# dice2.net
KiCad netlist of a schematic drawn in EAGLE
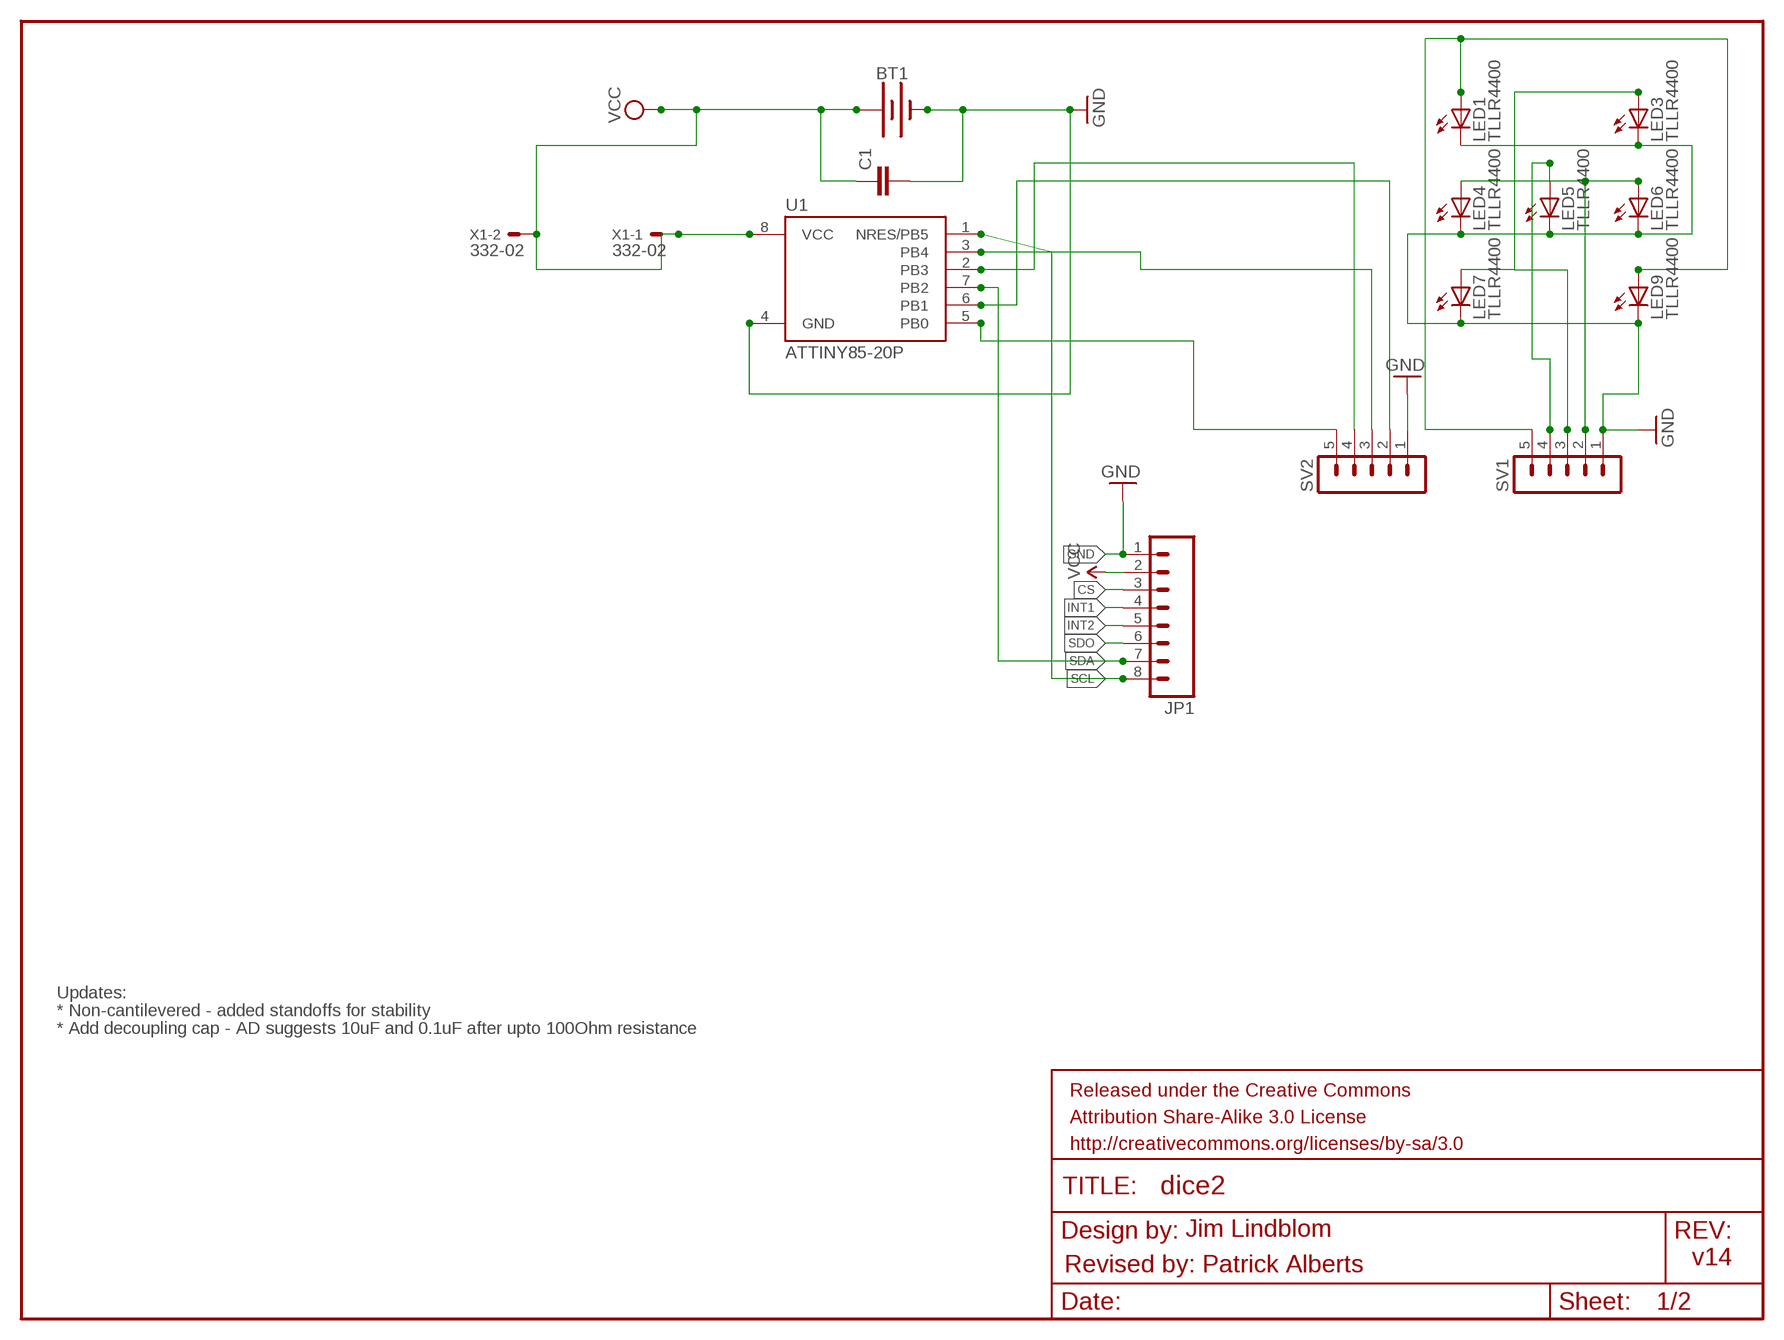
[diagram p0: schematic, sheet 1]

(export (version "E")
  (design (tool "Eeschema 10.0.6"))
  (components
    (comp (ref "BT1")
      (value "BATTERY-20MM_PTH")
      (footprint "eagle-import:BATTCOM_20MM_PTH")
      (libsource (lib "eagle-import") (part "BATTERY-20MM_PTH"))
    )
    (comp (ref "C1")
      (value "C-EU025-024X044")
      (footprint "eagle-import:C025-024X044")
      (libsource (lib "eagle-import") (part "C-EU025-024X044"))
    )
    (comp (ref "JP1")
      (value "M08")
      (footprint "eagle-import:1X08")
      (libsource (lib "eagle-import") (part "M08"))
    )
    (comp (ref "LED1")
      (value "TLLR4400")
      (footprint "eagle-import:LED3MM")
      (fields (field (name "MF") "VISHAY SEMICONDUCTOR"))
      (libsource (lib "eagle-import") (part "TLLR4400"))
    )
    (comp (ref "LED3")
      (value "TLLR4400")
      (footprint "eagle-import:LED3MM")
      (fields (field (name "MF") "VISHAY SEMICONDUCTOR"))
      (libsource (lib "eagle-import") (part "TLLR4400"))
    )
    (comp (ref "LED4")
      (value "TLLR4400")
      (footprint "eagle-import:LED3MM")
      (fields (field (name "MF") "VISHAY SEMICONDUCTOR"))
      (libsource (lib "eagle-import") (part "TLLR4400"))
    )
    (comp (ref "LED5")
      (value "TLLR4400")
      (footprint "eagle-import:LED3MM")
      (fields (field (name "MF") "VISHAY SEMICONDUCTOR"))
      (libsource (lib "eagle-import") (part "TLLR4400"))
    )
    (comp (ref "LED6")
      (value "TLLR4400")
      (footprint "eagle-import:LED3MM")
      (fields (field (name "MF") "VISHAY SEMICONDUCTOR"))
      (libsource (lib "eagle-import") (part "TLLR4400"))
    )
    (comp (ref "LED7")
      (value "TLLR4400")
      (footprint "eagle-import:LED3MM")
      (fields (field (name "MF") "VISHAY SEMICONDUCTOR"))
      (libsource (lib "eagle-import") (part "TLLR4400"))
    )
    (comp (ref "LED9")
      (value "TLLR4400")
      (footprint "eagle-import:LED3MM")
      (fields (field (name "MF") "VISHAY SEMICONDUCTOR"))
      (libsource (lib "eagle-import") (part "TLLR4400"))
    )
    (comp (ref "SV1")
      (value "MA05-1")
      (footprint "eagle-import:MA05-1")
      (libsource (lib "eagle-import") (part "MA05-1"))
    )
    (comp (ref "SV2")
      (value "MA05-1")
      (footprint "eagle-import:MA05-1")
      (libsource (lib "eagle-import") (part "MA05-1"))
    )
    (comp (ref "U1")
      (value "ATTINY85-20P")
      (footprint "eagle-import:PDIP08_300MIL")
      (libsource (lib "eagle-import") (part "ATTINY85P-20"))
    )
    (comp (ref "X1")
      (value "332-02")
      (footprint "eagle-import:332-02")
      (libsource (lib "eagle-import") (part "332-02"))
    )
  )
  (nets
    (net (code "1") (name "CS") (class "Default")
      (node (ref "JP1") (pin "3") (pinfunction "3_3") (pintype "passive"))
    )
    (net (code "2") (name "GND") (class "Default")
      (node (ref "BT1") (pin "2") (pinfunction "-_2") (pintype "power_in"))
      (node (ref "C1") (pin "2") (pinfunction "2_2") (pintype "passive"))
      (node (ref "JP1") (pin "1") (pinfunction "1_1") (pintype "passive"))
      (node (ref "LED1") (pin "K") (pinfunction "C_K") (pintype "passive"))
      (node (ref "LED3") (pin "K") (pinfunction "C_K") (pintype "passive"))
      (node (ref "LED4") (pin "K") (pinfunction "C_K") (pintype "passive"))
      (node (ref "LED5") (pin "K") (pinfunction "C_K") (pintype "passive"))
      (node (ref "LED6") (pin "K") (pinfunction "C_K") (pintype "passive"))
      (node (ref "LED7") (pin "K") (pinfunction "C_K") (pintype "passive"))
      (node (ref "LED9") (pin "K") (pinfunction "C_K") (pintype "passive"))
      (node (ref "SV1") (pin "1") (pinfunction "1_1") (pintype "passive"))
      (node (ref "SV2") (pin "1") (pinfunction "1_1") (pintype "passive"))
      (node (ref "U1") (pin "4") (pinfunction "GND_4") (pintype "power_in"))
    )
    (net (code "3") (name "INT1") (class "Default")
      (node (ref "JP1") (pin "4") (pinfunction "4_4") (pintype "passive"))
    )
    (net (code "4") (name "INT2") (class "Default")
      (node (ref "JP1") (pin "5") (pinfunction "5_5") (pintype "passive"))
    )
    (net (code "5") (name "Net-(LED1-PadA)") (class "Default")
      (node (ref "LED1") (pin "A") (pinfunction "A_A") (pintype "passive"))
      (node (ref "LED9") (pin "A") (pinfunction "A_A") (pintype "passive"))
      (node (ref "SV1") (pin "5") (pinfunction "5_5") (pintype "passive"))
    )
    (net (code "6") (name "Net-(LED3-PadA)") (class "Default")
      (node (ref "LED3") (pin "A") (pinfunction "A_A") (pintype "passive"))
      (node (ref "LED7") (pin "A") (pinfunction "A_A") (pintype "passive"))
      (node (ref "SV1") (pin "3") (pinfunction "3_3") (pintype "passive"))
    )
    (net (code "7") (name "Net-(LED4-PadA)") (class "Default")
      (node (ref "LED4") (pin "A") (pinfunction "A_A") (pintype "passive"))
      (node (ref "LED6") (pin "A") (pinfunction "A_A") (pintype "passive"))
      (node (ref "SV1") (pin "2") (pinfunction "2_2") (pintype "passive"))
    )
    (net (code "8") (name "Net-(LED5-PadA)") (class "Default")
      (node (ref "LED5") (pin "A") (pinfunction "A_A") (pintype "passive"))
      (node (ref "SV1") (pin "4") (pinfunction "4_4") (pintype "passive"))
    )
    (net (code "9") (name "Net-(U1-PB0)") (class "Default")
      (node (ref "SV2") (pin "5") (pinfunction "5_5") (pintype "passive"))
      (node (ref "U1") (pin "5") (pinfunction "PB0_5") (pintype "bidirectional"))
    )
    (net (code "10") (name "Net-(U1-PB1)") (class "Default")
      (node (ref "SV2") (pin "2") (pinfunction "2_2") (pintype "passive"))
      (node (ref "U1") (pin "6") (pinfunction "PB1_6") (pintype "bidirectional"))
    )
    (net (code "11") (name "Net-(U1-PB3)") (class "Default")
      (node (ref "SV2") (pin "4") (pinfunction "4_4") (pintype "passive"))
      (node (ref "U1") (pin "2") (pinfunction "PB3_2") (pintype "bidirectional"))
    )
    (net (code "12") (name "Net-(U1-PB4)") (class "Default")
      (node (ref "SV2") (pin "3") (pinfunction "3_3") (pintype "passive"))
      (node (ref "U1") (pin "3") (pinfunction "PB4_3") (pintype "bidirectional"))
    )
    (net (code "13") (name "SCL") (class "Default")
      (node (ref "JP1") (pin "8") (pinfunction "8_8") (pintype "passive"))
      (node (ref "U1") (pin "1") (pinfunction "NRES/PB5_1") (pintype "bidirectional"))
    )
    (net (code "14") (name "SDA") (class "Default")
      (node (ref "JP1") (pin "7") (pinfunction "7_7") (pintype "passive"))
      (node (ref "U1") (pin "7") (pinfunction "PB2_7") (pintype "bidirectional"))
    )
    (net (code "15") (name "SDO") (class "Default")
      (node (ref "JP1") (pin "6") (pinfunction "6_6") (pintype "passive"))
    )
    (net (code "16") (name "VCC") (class "Default")
      (node (ref "BT1") (pin "1") (pinfunction "+_1") (pintype "power_in"))
      (node (ref "C1") (pin "1") (pinfunction "1_1") (pintype "passive"))
      (node (ref "JP1") (pin "2") (pinfunction "2_2") (pintype "passive"))
      (node (ref "U1") (pin "8") (pinfunction "VCC_8") (pintype "power_in"))
      (node (ref "X1") (pin "1") (pinfunction "S_1") (pintype "passive"))
      (node (ref "X1") (pin "2") (pinfunction "S_2") (pintype "passive"))
    )
  )
)
